# h-bridge-relay.net
KiCad netlist of a schematic drawn in EAGLE
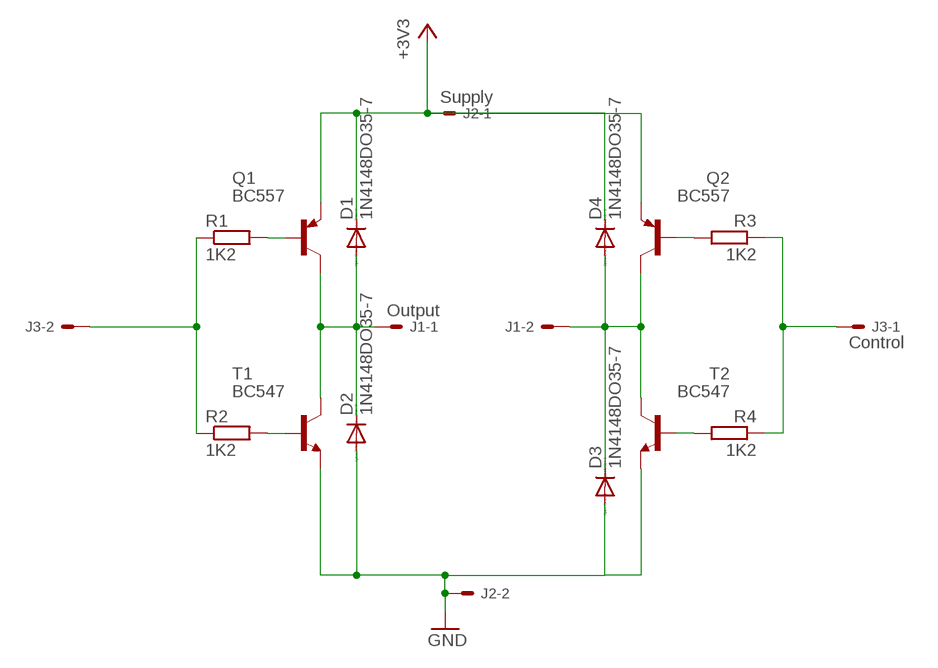
[diagram p0: schematic, sheet 1]

(export (version "E")
  (design (tool "Eeschema 10.0.6"))
  (components
    (comp (ref "D1")
      (value "1N4148DO35-7")
      (footprint "eagle-import:DO35-7")
      (libsource (lib "eagle-import") (part "1N4148DO35-7"))
    )
    (comp (ref "D2")
      (value "1N4148DO35-7")
      (footprint "eagle-import:DO35-7")
      (libsource (lib "eagle-import") (part "1N4148DO35-7"))
    )
    (comp (ref "D3")
      (value "1N4148DO35-7")
      (footprint "eagle-import:DO35-7")
      (libsource (lib "eagle-import") (part "1N4148DO35-7"))
    )
    (comp (ref "D4")
      (value "1N4148DO35-7")
      (footprint "eagle-import:DO35-7")
      (libsource (lib "eagle-import") (part "1N4148DO35-7"))
    )
    (comp (ref "J1")
      (value "Output")
      (footprint "eagle-import:6410-02")
      (libsource (lib "eagle-import") (part "22-?-0227-2021"))
    )
    (comp (ref "J2")
      (value "Supply")
      (footprint "eagle-import:6410-02")
      (libsource (lib "eagle-import") (part "22-?-0227-2021"))
    )
    (comp (ref "J3")
      (value "Control")
      (footprint "eagle-import:6410-02")
      (libsource (lib "eagle-import") (part "22-?-0227-2021"))
    )
    (comp (ref "Q1")
      (value "BC557")
      (footprint "eagle-import:TO92")
      (libsource (lib "eagle-import") (part "BC557"))
    )
    (comp (ref "Q2")
      (value "BC557")
      (footprint "eagle-import:TO92")
      (libsource (lib "eagle-import") (part "BC557"))
    )
    (comp (ref "R1")
      (value "1K2")
      (footprint "eagle-import:0207_7")
      (libsource (lib "eagle-import") (part "R-EU_0207/7"))
    )
    (comp (ref "R2")
      (value "1K2")
      (footprint "eagle-import:0207_12")
      (libsource (lib "eagle-import") (part "R-EU_0207/12"))
    )
    (comp (ref "R3")
      (value "1K2")
      (footprint "eagle-import:0207_2V")
      (libsource (lib "eagle-import") (part "R-EU_0207/2V"))
    )
    (comp (ref "R4")
      (value "1K2")
      (footprint "eagle-import:0207_7")
      (libsource (lib "eagle-import") (part "R-EU_0207/7"))
    )
    (comp (ref "T1")
      (value "BC547")
      (footprint "eagle-import:TO92")
      (libsource (lib "eagle-import") (part "BC547"))
    )
    (comp (ref "T2")
      (value "BC547")
      (footprint "eagle-import:TO92")
      (libsource (lib "eagle-import") (part "BC547"))
    )
  )
  (nets
    (net (code "1") (name "+3V3") (class "Default")
      (node (ref "D1") (pin "C") (pinfunction "C_C") (pintype "passive"))
      (node (ref "D4") (pin "C") (pinfunction "C_C") (pintype "passive"))
      (node (ref "J2") (pin "1") (pinfunction "S_1") (pintype "passive"))
      (node (ref "Q1") (pin "1") (pinfunction "E_1") (pintype "passive"))
      (node (ref "Q2") (pin "1") (pinfunction "E_1") (pintype "passive"))
    )
    (net (code "2") (name "GND") (class "Default")
      (node (ref "D2") (pin "A") (pinfunction "A_A") (pintype "passive"))
      (node (ref "D3") (pin "A") (pinfunction "A_A") (pintype "passive"))
      (node (ref "J2") (pin "2") (pinfunction "S_2") (pintype "passive"))
      (node (ref "T1") (pin "1") (pinfunction "E_1") (pintype "passive"))
      (node (ref "T2") (pin "1") (pinfunction "E_1") (pintype "passive"))
    )
    (net (code "3") (name "Net-(J1A-S)") (class "Default")
      (node (ref "D1") (pin "A") (pinfunction "A_A") (pintype "passive"))
      (node (ref "D2") (pin "C") (pinfunction "C_C") (pintype "passive"))
      (node (ref "J1") (pin "1") (pinfunction "S_1") (pintype "passive"))
      (node (ref "Q1") (pin "3") (pinfunction "C_3") (pintype "passive"))
      (node (ref "T1") (pin "3") (pinfunction "C_3") (pintype "passive"))
    )
    (net (code "4") (name "Net-(J1B-S)") (class "Default")
      (node (ref "D3") (pin "C") (pinfunction "C_C") (pintype "passive"))
      (node (ref "D4") (pin "A") (pinfunction "A_A") (pintype "passive"))
      (node (ref "J1") (pin "2") (pinfunction "S_2") (pintype "passive"))
      (node (ref "Q2") (pin "3") (pinfunction "C_3") (pintype "passive"))
      (node (ref "T2") (pin "3") (pinfunction "C_3") (pintype "passive"))
    )
    (net (code "5") (name "Net-(J3A-S)") (class "Default")
      (node (ref "J3") (pin "1") (pinfunction "S_1") (pintype "passive"))
      (node (ref "R3") (pin "1") (pinfunction "1_1") (pintype "passive"))
      (node (ref "R4") (pin "1") (pinfunction "1_1") (pintype "passive"))
    )
    (net (code "6") (name "Net-(J3B-S)") (class "Default")
      (node (ref "J3") (pin "2") (pinfunction "S_2") (pintype "passive"))
      (node (ref "R1") (pin "1") (pinfunction "1_1") (pintype "passive"))
      (node (ref "R2") (pin "1") (pinfunction "1_1") (pintype "passive"))
    )
    (net (code "7") (name "Net-(Q1-B)") (class "Default")
      (node (ref "Q1") (pin "2") (pinfunction "B_2") (pintype "passive"))
      (node (ref "R1") (pin "2") (pinfunction "2_2") (pintype "passive"))
    )
    (net (code "8") (name "Net-(Q2-B)") (class "Default")
      (node (ref "Q2") (pin "2") (pinfunction "B_2") (pintype "passive"))
      (node (ref "R3") (pin "2") (pinfunction "2_2") (pintype "passive"))
    )
    (net (code "9") (name "Net-(T1-B)") (class "Default")
      (node (ref "R2") (pin "2") (pinfunction "2_2") (pintype "passive"))
      (node (ref "T1") (pin "2") (pinfunction "B_2") (pintype "passive"))
    )
    (net (code "10") (name "Net-(T2-B)") (class "Default")
      (node (ref "R4") (pin "2") (pinfunction "2_2") (pintype "passive"))
      (node (ref "T2") (pin "2") (pinfunction "B_2") (pintype "passive"))
    )
  )
)
